# io.net
KiCad netlist of a schematic drawn in EAGLE
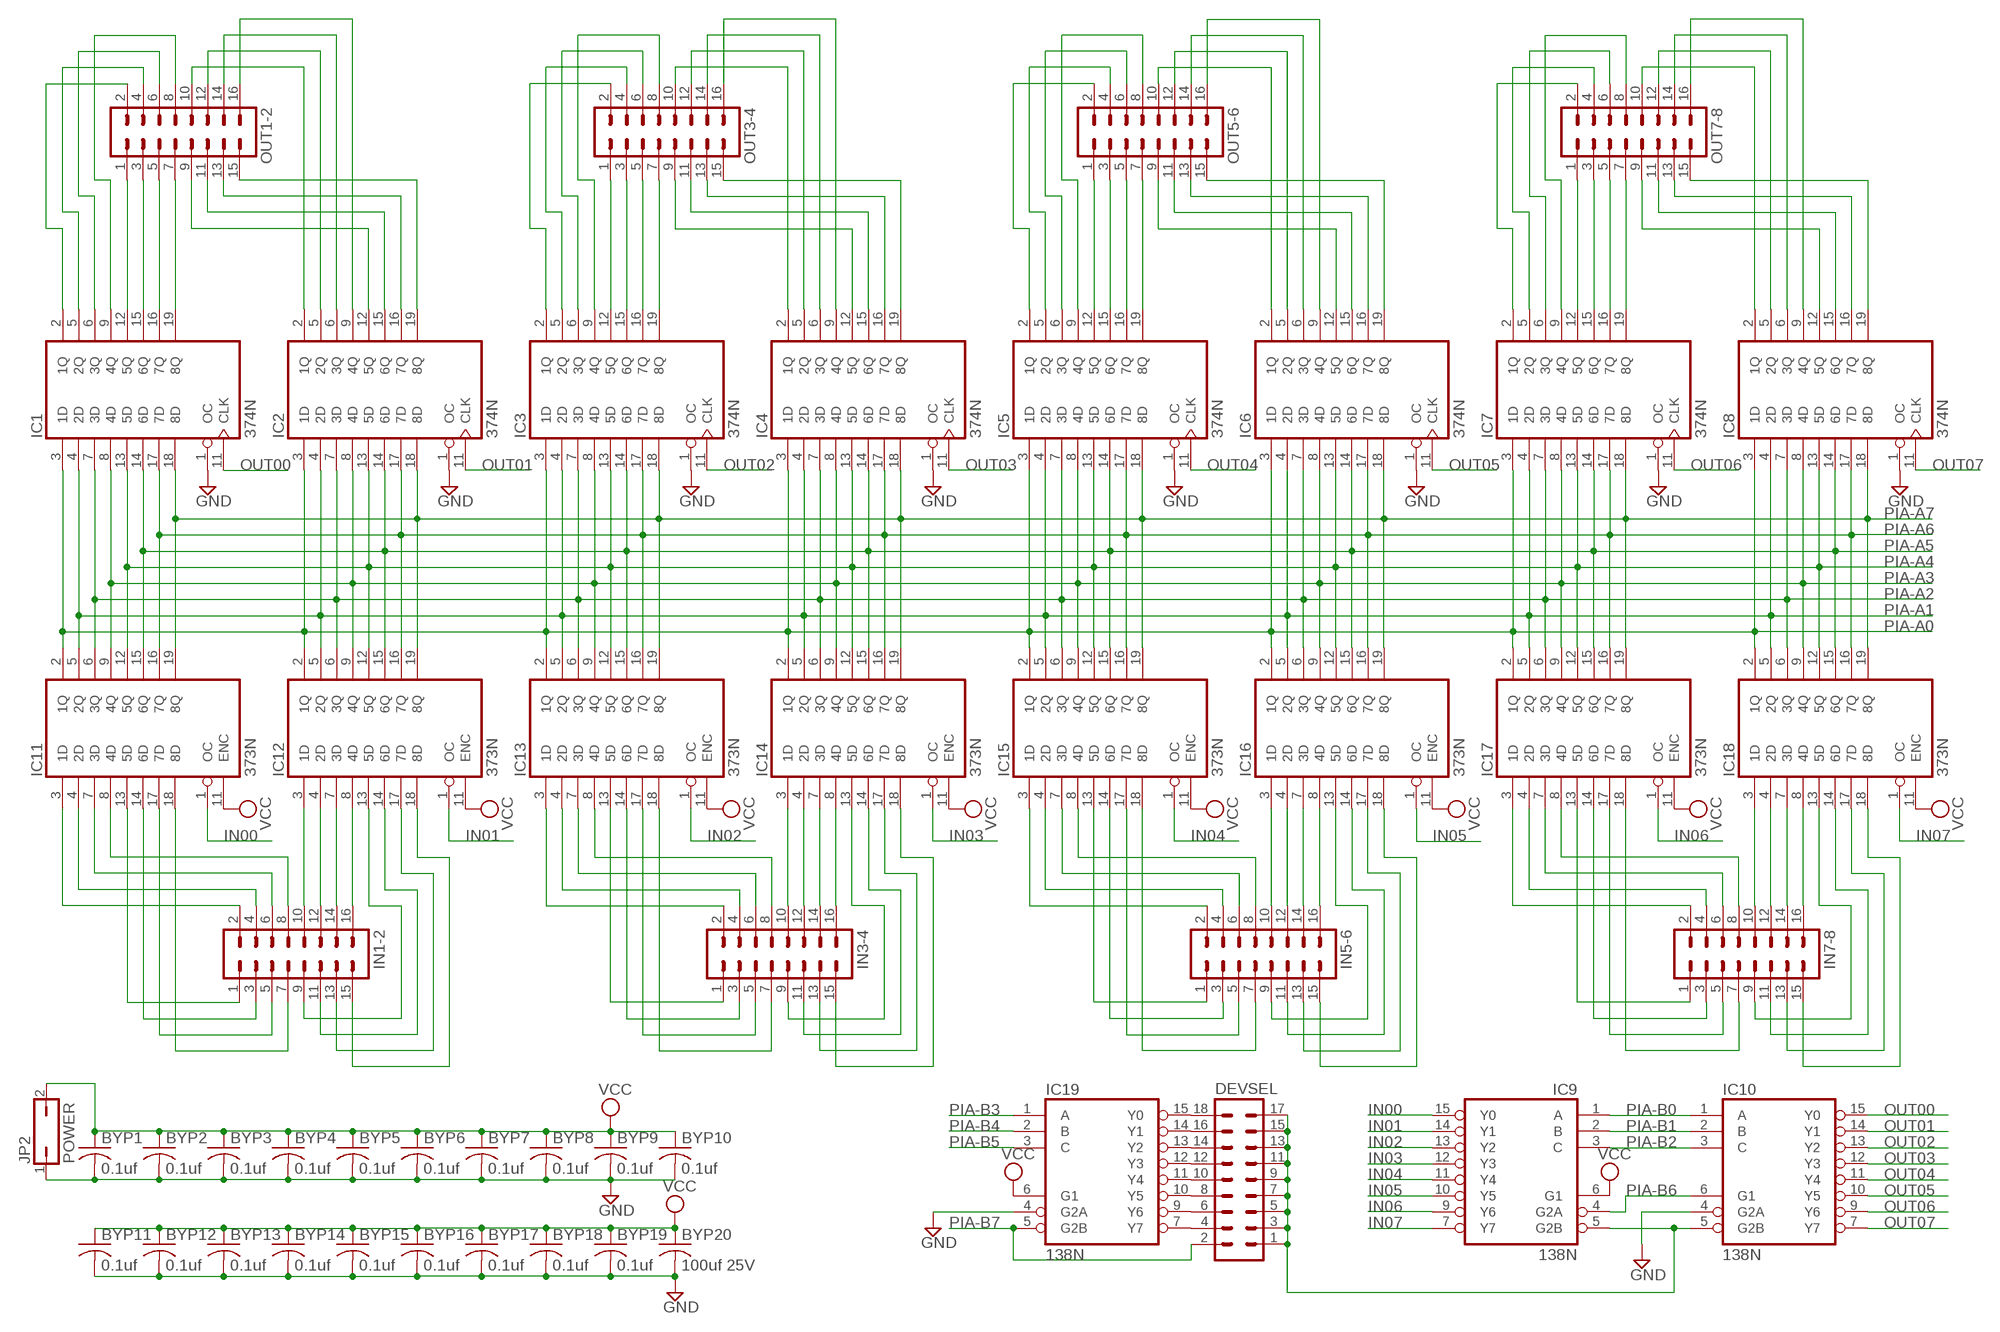
[diagram p0: schematic, sheet 1]
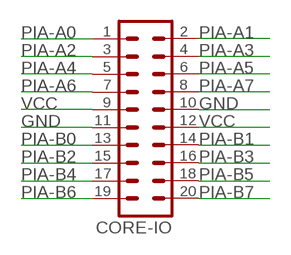
[diagram p1: schematic, sheet 2]

(export (version "E")
  (design (tool "Eeschema 10.0.6"))
  (components
    (comp (ref "CORE-IO")
      (value "MA10-2")
      (footprint "eagle-import:MA10-2")
      (libsource (lib "eagle-import") (part "MA10-2"))
    )
    (comp (ref "BYP1")
      (value "0.1uf")
      (footprint "eagle-import:C050-025X075")
      (libsource (lib "eagle-import") (part "C-US050-025X075"))
    )
    (comp (ref "BYP2")
      (value "0.1uf")
      (footprint "eagle-import:C050-025X075")
      (libsource (lib "eagle-import") (part "C-US050-025X075"))
    )
    (comp (ref "BYP3")
      (value "0.1uf")
      (footprint "eagle-import:C050-025X075")
      (libsource (lib "eagle-import") (part "C-US050-025X075"))
    )
    (comp (ref "BYP4")
      (value "0.1uf")
      (footprint "eagle-import:C050-025X075")
      (libsource (lib "eagle-import") (part "C-US050-025X075"))
    )
    (comp (ref "BYP5")
      (value "0.1uf")
      (footprint "eagle-import:C050-025X075")
      (libsource (lib "eagle-import") (part "C-US050-025X075"))
    )
    (comp (ref "BYP6")
      (value "0.1uf")
      (footprint "eagle-import:C050-025X075")
      (libsource (lib "eagle-import") (part "C-US050-025X075"))
    )
    (comp (ref "BYP7")
      (value "0.1uf")
      (footprint "eagle-import:C050-025X075")
      (libsource (lib "eagle-import") (part "C-US050-025X075"))
    )
    (comp (ref "BYP8")
      (value "0.1uf")
      (footprint "eagle-import:C050-025X075")
      (libsource (lib "eagle-import") (part "C-US050-025X075"))
    )
    (comp (ref "BYP9")
      (value "0.1uf")
      (footprint "eagle-import:C050-025X075")
      (libsource (lib "eagle-import") (part "C-US050-025X075"))
    )
    (comp (ref "BYP10")
      (value "0.1uf")
      (footprint "eagle-import:C050-025X075")
      (libsource (lib "eagle-import") (part "C-US050-025X075"))
    )
    (comp (ref "BYP11")
      (value "0.1uf")
      (footprint "eagle-import:C050-025X075")
      (libsource (lib "eagle-import") (part "C-US050-025X075"))
    )
    (comp (ref "BYP12")
      (value "0.1uf")
      (footprint "eagle-import:C050-025X075")
      (libsource (lib "eagle-import") (part "C-US050-025X075"))
    )
    (comp (ref "BYP13")
      (value "0.1uf")
      (footprint "eagle-import:C050-025X075")
      (libsource (lib "eagle-import") (part "C-US050-025X075"))
    )
    (comp (ref "BYP14")
      (value "0.1uf")
      (footprint "eagle-import:C050-025X075")
      (libsource (lib "eagle-import") (part "C-US050-025X075"))
    )
    (comp (ref "BYP15")
      (value "0.1uf")
      (footprint "eagle-import:C050-025X075")
      (libsource (lib "eagle-import") (part "C-US050-025X075"))
    )
    (comp (ref "BYP16")
      (value "0.1uf")
      (footprint "eagle-import:C050-025X075")
      (libsource (lib "eagle-import") (part "C-US050-025X075"))
    )
    (comp (ref "BYP17")
      (value "0.1uf")
      (footprint "eagle-import:C050-025X075")
      (libsource (lib "eagle-import") (part "C-US050-025X075"))
    )
    (comp (ref "BYP18")
      (value "0.1uf")
      (footprint "eagle-import:C050-025X075")
      (libsource (lib "eagle-import") (part "C-US050-025X075"))
    )
    (comp (ref "BYP19")
      (value "0.1uf")
      (footprint "eagle-import:C050-025X075")
      (libsource (lib "eagle-import") (part "C-US050-025X075"))
    )
    (comp (ref "BYP20")
      (value "100uf 25V")
      (footprint "eagle-import:C150-064X183")
      (libsource (lib "eagle-import") (part "C-US150-064X183"))
    )
    (comp (ref "DEVSEL")
      (value "MA09-2")
      (footprint "eagle-import:MA09-2")
      (libsource (lib "eagle-import") (part "MA09-2"))
    )
    (comp (ref "IC1")
      (value "374N")
      (footprint "eagle-import:DIL20")
      (libsource (lib "eagle-import") (part "74374NLS"))
    )
    (comp (ref "IC2")
      (value "374N")
      (footprint "eagle-import:DIL20")
      (libsource (lib "eagle-import") (part "74374NLS"))
    )
    (comp (ref "IC3")
      (value "374N")
      (footprint "eagle-import:DIL20")
      (libsource (lib "eagle-import") (part "74374NLS"))
    )
    (comp (ref "IC4")
      (value "374N")
      (footprint "eagle-import:DIL20")
      (libsource (lib "eagle-import") (part "74374NLS"))
    )
    (comp (ref "IC5")
      (value "374N")
      (footprint "eagle-import:DIL20")
      (libsource (lib "eagle-import") (part "74374NLS"))
    )
    (comp (ref "IC6")
      (value "374N")
      (footprint "eagle-import:DIL20")
      (libsource (lib "eagle-import") (part "74374NLS"))
    )
    (comp (ref "IC7")
      (value "374N")
      (footprint "eagle-import:DIL20")
      (libsource (lib "eagle-import") (part "74374NLS"))
    )
    (comp (ref "IC8")
      (value "374N")
      (footprint "eagle-import:DIL20")
      (libsource (lib "eagle-import") (part "74374NLS"))
    )
    (comp (ref "IC9")
      (value "138N")
      (footprint "eagle-import:DIL16")
      (libsource (lib "eagle-import") (part "74138NLS"))
    )
    (comp (ref "IC10")
      (value "138N")
      (footprint "eagle-import:DIL16")
      (libsource (lib "eagle-import") (part "74138NLS"))
    )
    (comp (ref "IC11")
      (value "373N")
      (footprint "eagle-import:DIL20")
      (libsource (lib "eagle-import") (part "74373NLS"))
    )
    (comp (ref "IC12")
      (value "373N")
      (footprint "eagle-import:DIL20")
      (libsource (lib "eagle-import") (part "74373NLS"))
    )
    (comp (ref "IC13")
      (value "373N")
      (footprint "eagle-import:DIL20")
      (libsource (lib "eagle-import") (part "74373NLS"))
    )
    (comp (ref "IC14")
      (value "373N")
      (footprint "eagle-import:DIL20")
      (libsource (lib "eagle-import") (part "74373NLS"))
    )
    (comp (ref "IC15")
      (value "373N")
      (footprint "eagle-import:DIL20")
      (libsource (lib "eagle-import") (part "74373NLS"))
    )
    (comp (ref "IC16")
      (value "373N")
      (footprint "eagle-import:DIL20")
      (libsource (lib "eagle-import") (part "74373NLS"))
    )
    (comp (ref "IC17")
      (value "373N")
      (footprint "eagle-import:DIL20")
      (libsource (lib "eagle-import") (part "74373NLS"))
    )
    (comp (ref "IC18")
      (value "373N")
      (footprint "eagle-import:DIL20")
      (libsource (lib "eagle-import") (part "74373NLS"))
    )
    (comp (ref "IC19")
      (value "138N")
      (footprint "eagle-import:DIL16")
      (libsource (lib "eagle-import") (part "74138NLS"))
    )
    (comp (ref "IN1-2")
      (value "MA08-2")
      (footprint "eagle-import:MA08-2")
      (libsource (lib "eagle-import") (part "MA08-2"))
    )
    (comp (ref "IN3-4")
      (value "MA08-2")
      (footprint "eagle-import:MA08-2")
      (libsource (lib "eagle-import") (part "MA08-2"))
    )
    (comp (ref "IN5-6")
      (value "MA08-2")
      (footprint "eagle-import:MA08-2")
      (libsource (lib "eagle-import") (part "MA08-2"))
    )
    (comp (ref "IN7-8")
      (value "MA08-2")
      (footprint "eagle-import:MA08-2")
      (libsource (lib "eagle-import") (part "MA08-2"))
    )
    (comp (ref "JP2")
      (value "POWER")
      (footprint "eagle-import:JP1")
      (libsource (lib "eagle-import") (part "JP1Q"))
    )
    (comp (ref "OUT1-2")
      (value "MA08-2")
      (footprint "eagle-import:MA08-2")
      (libsource (lib "eagle-import") (part "MA08-2"))
    )
    (comp (ref "OUT3-4")
      (value "MA08-2")
      (footprint "eagle-import:MA08-2")
      (libsource (lib "eagle-import") (part "MA08-2"))
    )
    (comp (ref "OUT5-6")
      (value "MA08-2")
      (footprint "eagle-import:MA08-2")
      (libsource (lib "eagle-import") (part "MA08-2"))
    )
    (comp (ref "OUT7-8")
      (value "MA08-2")
      (footprint "eagle-import:MA08-2")
      (libsource (lib "eagle-import") (part "MA08-2"))
    )
  )
  (nets
    (net (code "1") (name "GND") (class "Default")
      (node (ref "BYP1") (pin "2") (pinfunction "2_2") (pintype "passive"))
      (node (ref "BYP10") (pin "2") (pinfunction "2_2") (pintype "passive"))
      (node (ref "BYP11") (pin "2") (pinfunction "2_2") (pintype "passive"))
      (node (ref "BYP12") (pin "2") (pinfunction "2_2") (pintype "passive"))
      (node (ref "BYP13") (pin "2") (pinfunction "2_2") (pintype "passive"))
      (node (ref "BYP14") (pin "2") (pinfunction "2_2") (pintype "passive"))
      (node (ref "BYP15") (pin "2") (pinfunction "2_2") (pintype "passive"))
      (node (ref "BYP16") (pin "2") (pinfunction "2_2") (pintype "passive"))
      (node (ref "BYP17") (pin "2") (pinfunction "2_2") (pintype "passive"))
      (node (ref "BYP18") (pin "2") (pinfunction "2_2") (pintype "passive"))
      (node (ref "BYP19") (pin "2") (pinfunction "2_2") (pintype "passive"))
      (node (ref "BYP2") (pin "2") (pinfunction "2_2") (pintype "passive"))
      (node (ref "BYP20") (pin "2") (pinfunction "2_2") (pintype "passive"))
      (node (ref "BYP3") (pin "2") (pinfunction "2_2") (pintype "passive"))
      (node (ref "BYP4") (pin "2") (pinfunction "2_2") (pintype "passive"))
      (node (ref "BYP5") (pin "2") (pinfunction "2_2") (pintype "passive"))
      (node (ref "BYP6") (pin "2") (pinfunction "2_2") (pintype "passive"))
      (node (ref "BYP7") (pin "2") (pinfunction "2_2") (pintype "passive"))
      (node (ref "BYP8") (pin "2") (pinfunction "2_2") (pintype "passive"))
      (node (ref "BYP9") (pin "2") (pinfunction "2_2") (pintype "passive"))
      (node (ref "CORE-IO") (pin "10") (pinfunction "10_10") (pintype "passive"))
      (node (ref "CORE-IO") (pin "11") (pinfunction "11_11") (pintype "passive"))
      (node (ref "IC1") (pin "1") (pinfunction "OC_1") (pintype "input"))
      (node (ref "IC10") (pin "4") (pinfunction "G2A_4") (pintype "input"))
      (node (ref "IC19") (pin "4") (pinfunction "G2A_4") (pintype "input"))
      (node (ref "IC2") (pin "1") (pinfunction "OC_1") (pintype "input"))
      (node (ref "IC3") (pin "1") (pinfunction "OC_1") (pintype "input"))
      (node (ref "IC4") (pin "1") (pinfunction "OC_1") (pintype "input"))
      (node (ref "IC5") (pin "1") (pinfunction "OC_1") (pintype "input"))
      (node (ref "IC6") (pin "1") (pinfunction "OC_1") (pintype "input"))
      (node (ref "IC7") (pin "1") (pinfunction "OC_1") (pintype "input"))
      (node (ref "IC8") (pin "1") (pinfunction "OC_1") (pintype "input"))
      (node (ref "JP2") (pin "1") (pinfunction "1_1") (pintype "passive"))
    )
    (net (code "2") (name "IN00") (class "Default")
      (node (ref "IC11") (pin "1") (pinfunction "OC_1") (pintype "input"))
      (node (ref "IC9") (pin "15") (pinfunction "Y0_15") (pintype "output"))
    )
    (net (code "3") (name "IN01") (class "Default")
      (node (ref "IC12") (pin "1") (pinfunction "OC_1") (pintype "input"))
      (node (ref "IC9") (pin "14") (pinfunction "Y1_14") (pintype "output"))
    )
    (net (code "4") (name "IN02") (class "Default")
      (node (ref "IC13") (pin "1") (pinfunction "OC_1") (pintype "input"))
      (node (ref "IC9") (pin "13") (pinfunction "Y2_13") (pintype "output"))
    )
    (net (code "5") (name "IN03") (class "Default")
      (node (ref "IC14") (pin "1") (pinfunction "OC_1") (pintype "input"))
      (node (ref "IC9") (pin "12") (pinfunction "Y3_12") (pintype "output"))
    )
    (net (code "6") (name "IN04") (class "Default")
      (node (ref "IC15") (pin "1") (pinfunction "OC_1") (pintype "input"))
      (node (ref "IC9") (pin "11") (pinfunction "Y4_11") (pintype "output"))
    )
    (net (code "7") (name "IN05") (class "Default")
      (node (ref "IC16") (pin "1") (pinfunction "OC_1") (pintype "input"))
      (node (ref "IC9") (pin "10") (pinfunction "Y5_10") (pintype "output"))
    )
    (net (code "8") (name "IN06") (class "Default")
      (node (ref "IC17") (pin "1") (pinfunction "OC_1") (pintype "input"))
      (node (ref "IC9") (pin "9") (pinfunction "Y6_9") (pintype "output"))
    )
    (net (code "9") (name "IN07") (class "Default")
      (node (ref "IC18") (pin "1") (pinfunction "OC_1") (pintype "input"))
      (node (ref "IC9") (pin "7") (pinfunction "Y7_7") (pintype "output"))
    )
    (net (code "10") (name "Net-(IC1A-1Q)") (class "Default")
      (node (ref "IC1") (pin "2") (pinfunction "1Q_2") (pintype "tri_state"))
      (node (ref "OUT1-2") (pin "2") (pinfunction "2_2") (pintype "passive"))
    )
    (net (code "11") (name "Net-(IC1A-2Q)") (class "Default")
      (node (ref "IC1") (pin "5") (pinfunction "2Q_5") (pintype "tri_state"))
      (node (ref "OUT1-2") (pin "4") (pinfunction "4_4") (pintype "passive"))
    )
    (net (code "12") (name "Net-(IC1A-3Q)") (class "Default")
      (node (ref "IC1") (pin "6") (pinfunction "3Q_6") (pintype "tri_state"))
      (node (ref "OUT1-2") (pin "6") (pinfunction "6_6") (pintype "passive"))
    )
    (net (code "13") (name "Net-(IC1A-4Q)") (class "Default")
      (node (ref "IC1") (pin "9") (pinfunction "4Q_9") (pintype "tri_state"))
      (node (ref "OUT1-2") (pin "8") (pinfunction "8_8") (pintype "passive"))
    )
    (net (code "14") (name "Net-(IC1A-5Q)") (class "Default")
      (node (ref "IC1") (pin "12") (pinfunction "5Q_12") (pintype "tri_state"))
      (node (ref "OUT1-2") (pin "1") (pinfunction "1_1") (pintype "passive"))
    )
    (net (code "15") (name "Net-(IC1A-6Q)") (class "Default")
      (node (ref "IC1") (pin "15") (pinfunction "6Q_15") (pintype "tri_state"))
      (node (ref "OUT1-2") (pin "3") (pinfunction "3_3") (pintype "passive"))
    )
    (net (code "16") (name "Net-(IC1A-7Q)") (class "Default")
      (node (ref "IC1") (pin "16") (pinfunction "7Q_16") (pintype "tri_state"))
      (node (ref "OUT1-2") (pin "5") (pinfunction "5_5") (pintype "passive"))
    )
    (net (code "17") (name "Net-(IC1A-8Q)") (class "Default")
      (node (ref "IC1") (pin "19") (pinfunction "8Q_19") (pintype "tri_state"))
      (node (ref "OUT1-2") (pin "7") (pinfunction "7_7") (pintype "passive"))
    )
    (net (code "18") (name "Net-(IC2A-1Q)") (class "Default")
      (node (ref "IC2") (pin "2") (pinfunction "1Q_2") (pintype "tri_state"))
      (node (ref "OUT1-2") (pin "10") (pinfunction "10_10") (pintype "passive"))
    )
    (net (code "19") (name "Net-(IC2A-2Q)") (class "Default")
      (node (ref "IC2") (pin "5") (pinfunction "2Q_5") (pintype "tri_state"))
      (node (ref "OUT1-2") (pin "12") (pinfunction "12_12") (pintype "passive"))
    )
    (net (code "20") (name "Net-(IC2A-3Q)") (class "Default")
      (node (ref "IC2") (pin "6") (pinfunction "3Q_6") (pintype "tri_state"))
      (node (ref "OUT1-2") (pin "14") (pinfunction "14_14") (pintype "passive"))
    )
    (net (code "21") (name "Net-(IC2A-4Q)") (class "Default")
      (node (ref "IC2") (pin "9") (pinfunction "4Q_9") (pintype "tri_state"))
      (node (ref "OUT1-2") (pin "16") (pinfunction "16_16") (pintype "passive"))
    )
    (net (code "22") (name "Net-(IC2A-5Q)") (class "Default")
      (node (ref "IC2") (pin "12") (pinfunction "5Q_12") (pintype "tri_state"))
      (node (ref "OUT1-2") (pin "9") (pinfunction "9_9") (pintype "passive"))
    )
    (net (code "23") (name "Net-(IC2A-6Q)") (class "Default")
      (node (ref "IC2") (pin "15") (pinfunction "6Q_15") (pintype "tri_state"))
      (node (ref "OUT1-2") (pin "11") (pinfunction "11_11") (pintype "passive"))
    )
    (net (code "24") (name "Net-(IC2A-7Q)") (class "Default")
      (node (ref "IC2") (pin "16") (pinfunction "7Q_16") (pintype "tri_state"))
      (node (ref "OUT1-2") (pin "13") (pinfunction "13_13") (pintype "passive"))
    )
    (net (code "25") (name "Net-(IC2A-8Q)") (class "Default")
      (node (ref "IC2") (pin "19") (pinfunction "8Q_19") (pintype "tri_state"))
      (node (ref "OUT1-2") (pin "15") (pinfunction "15_15") (pintype "passive"))
    )
    (net (code "26") (name "Net-(IC3A-1Q)") (class "Default")
      (node (ref "IC3") (pin "2") (pinfunction "1Q_2") (pintype "tri_state"))
      (node (ref "OUT3-4") (pin "2") (pinfunction "2_2") (pintype "passive"))
    )
    (net (code "27") (name "Net-(IC3A-2Q)") (class "Default")
      (node (ref "IC3") (pin "5") (pinfunction "2Q_5") (pintype "tri_state"))
      (node (ref "OUT3-4") (pin "4") (pinfunction "4_4") (pintype "passive"))
    )
    (net (code "28") (name "Net-(IC3A-3Q)") (class "Default")
      (node (ref "IC3") (pin "6") (pinfunction "3Q_6") (pintype "tri_state"))
      (node (ref "OUT3-4") (pin "6") (pinfunction "6_6") (pintype "passive"))
    )
    (net (code "29") (name "Net-(IC3A-4Q)") (class "Default")
      (node (ref "IC3") (pin "9") (pinfunction "4Q_9") (pintype "tri_state"))
      (node (ref "OUT3-4") (pin "8") (pinfunction "8_8") (pintype "passive"))
    )
    (net (code "30") (name "Net-(IC3A-5Q)") (class "Default")
      (node (ref "IC3") (pin "12") (pinfunction "5Q_12") (pintype "tri_state"))
      (node (ref "OUT3-4") (pin "1") (pinfunction "1_1") (pintype "passive"))
    )
    (net (code "31") (name "Net-(IC3A-6Q)") (class "Default")
      (node (ref "IC3") (pin "15") (pinfunction "6Q_15") (pintype "tri_state"))
      (node (ref "OUT3-4") (pin "3") (pinfunction "3_3") (pintype "passive"))
    )
    (net (code "32") (name "Net-(IC3A-7Q)") (class "Default")
      (node (ref "IC3") (pin "16") (pinfunction "7Q_16") (pintype "tri_state"))
      (node (ref "OUT3-4") (pin "5") (pinfunction "5_5") (pintype "passive"))
    )
    (net (code "33") (name "Net-(IC3A-8Q)") (class "Default")
      (node (ref "IC3") (pin "19") (pinfunction "8Q_19") (pintype "tri_state"))
      (node (ref "OUT3-4") (pin "7") (pinfunction "7_7") (pintype "passive"))
    )
    (net (code "34") (name "Net-(IC4A-1Q)") (class "Default")
      (node (ref "IC4") (pin "2") (pinfunction "1Q_2") (pintype "tri_state"))
      (node (ref "OUT3-4") (pin "10") (pinfunction "10_10") (pintype "passive"))
    )
    (net (code "35") (name "Net-(IC4A-2Q)") (class "Default")
      (node (ref "IC4") (pin "5") (pinfunction "2Q_5") (pintype "tri_state"))
      (node (ref "OUT3-4") (pin "12") (pinfunction "12_12") (pintype "passive"))
    )
    (net (code "36") (name "Net-(IC4A-3Q)") (class "Default")
      (node (ref "IC4") (pin "6") (pinfunction "3Q_6") (pintype "tri_state"))
      (node (ref "OUT3-4") (pin "14") (pinfunction "14_14") (pintype "passive"))
    )
    (net (code "37") (name "Net-(IC4A-4Q)") (class "Default")
      (node (ref "IC4") (pin "9") (pinfunction "4Q_9") (pintype "tri_state"))
      (node (ref "OUT3-4") (pin "16") (pinfunction "16_16") (pintype "passive"))
    )
    (net (code "38") (name "Net-(IC4A-5Q)") (class "Default")
      (node (ref "IC4") (pin "12") (pinfunction "5Q_12") (pintype "tri_state"))
      (node (ref "OUT3-4") (pin "9") (pinfunction "9_9") (pintype "passive"))
    )
    (net (code "39") (name "Net-(IC4A-6Q)") (class "Default")
      (node (ref "IC4") (pin "15") (pinfunction "6Q_15") (pintype "tri_state"))
      (node (ref "OUT3-4") (pin "11") (pinfunction "11_11") (pintype "passive"))
    )
    (net (code "40") (name "Net-(IC4A-7Q)") (class "Default")
      (node (ref "IC4") (pin "16") (pinfunction "7Q_16") (pintype "tri_state"))
      (node (ref "OUT3-4") (pin "13") (pinfunction "13_13") (pintype "passive"))
    )
    (net (code "41") (name "Net-(IC4A-8Q)") (class "Default")
      (node (ref "IC4") (pin "19") (pinfunction "8Q_19") (pintype "tri_state"))
      (node (ref "OUT3-4") (pin "15") (pinfunction "15_15") (pintype "passive"))
    )
    (net (code "42") (name "Net-(IC5A-1Q)") (class "Default")
      (node (ref "IC5") (pin "2") (pinfunction "1Q_2") (pintype "tri_state"))
      (node (ref "OUT5-6") (pin "2") (pinfunction "2_2") (pintype "passive"))
    )
    (net (code "43") (name "Net-(IC5A-2Q)") (class "Default")
      (node (ref "IC5") (pin "5") (pinfunction "2Q_5") (pintype "tri_state"))
      (node (ref "OUT5-6") (pin "4") (pinfunction "4_4") (pintype "passive"))
    )
    (net (code "44") (name "Net-(IC5A-3Q)") (class "Default")
      (node (ref "IC5") (pin "6") (pinfunction "3Q_6") (pintype "tri_state"))
      (node (ref "OUT5-6") (pin "6") (pinfunction "6_6") (pintype "passive"))
    )
    (net (code "45") (name "Net-(IC5A-4Q)") (class "Default")
      (node (ref "IC5") (pin "9") (pinfunction "4Q_9") (pintype "tri_state"))
      (node (ref "OUT5-6") (pin "8") (pinfunction "8_8") (pintype "passive"))
    )
    (net (code "46") (name "Net-(IC5A-5Q)") (class "Default")
      (node (ref "IC5") (pin "12") (pinfunction "5Q_12") (pintype "tri_state"))
      (node (ref "OUT5-6") (pin "1") (pinfunction "1_1") (pintype "passive"))
    )
    (net (code "47") (name "Net-(IC5A-6Q)") (class "Default")
      (node (ref "IC5") (pin "15") (pinfunction "6Q_15") (pintype "tri_state"))
      (node (ref "OUT5-6") (pin "3") (pinfunction "3_3") (pintype "passive"))
    )
    (net (code "48") (name "Net-(IC5A-7Q)") (class "Default")
      (node (ref "IC5") (pin "16") (pinfunction "7Q_16") (pintype "tri_state"))
      (node (ref "OUT5-6") (pin "5") (pinfunction "5_5") (pintype "passive"))
    )
    (net (code "49") (name "Net-(IC5A-8Q)") (class "Default")
      (node (ref "IC5") (pin "19") (pinfunction "8Q_19") (pintype "tri_state"))
      (node (ref "OUT5-6") (pin "7") (pinfunction "7_7") (pintype "passive"))
    )
    (net (code "50") (name "Net-(IC6A-1Q)") (class "Default")
      (node (ref "IC6") (pin "2") (pinfunction "1Q_2") (pintype "tri_state"))
      (node (ref "OUT5-6") (pin "10") (pinfunction "10_10") (pintype "passive"))
    )
    (net (code "51") (name "Net-(IC6A-2Q)") (class "Default")
      (node (ref "IC6") (pin "5") (pinfunction "2Q_5") (pintype "tri_state"))
      (node (ref "OUT5-6") (pin "12") (pinfunction "12_12") (pintype "passive"))
    )
    (net (code "52") (name "Net-(IC6A-3Q)") (class "Default")
      (node (ref "IC6") (pin "6") (pinfunction "3Q_6") (pintype "tri_state"))
      (node (ref "OUT5-6") (pin "14") (pinfunction "14_14") (pintype "passive"))
    )
    (net (code "53") (name "Net-(IC6A-4Q)") (class "Default")
      (node (ref "IC6") (pin "9") (pinfunction "4Q_9") (pintype "tri_state"))
      (node (ref "OUT5-6") (pin "16") (pinfunction "16_16") (pintype "passive"))
    )
    (net (code "54") (name "Net-(IC6A-5Q)") (class "Default")
      (node (ref "IC6") (pin "12") (pinfunction "5Q_12") (pintype "tri_state"))
      (node (ref "OUT5-6") (pin "9") (pinfunction "9_9") (pintype "passive"))
    )
    (net (code "55") (name "Net-(IC6A-6Q)") (class "Default")
      (node (ref "IC6") (pin "15") (pinfunction "6Q_15") (pintype "tri_state"))
      (node (ref "OUT5-6") (pin "11") (pinfunction "11_11") (pintype "passive"))
    )
    (net (code "56") (name "Net-(IC6A-7Q)") (class "Default")
      (node (ref "IC6") (pin "16") (pinfunction "7Q_16") (pintype "tri_state"))
      (node (ref "OUT5-6") (pin "13") (pinfunction "13_13") (pintype "passive"))
    )
    (net (code "57") (name "Net-(IC6A-8Q)") (class "Default")
      (node (ref "IC6") (pin "19") (pinfunction "8Q_19") (pintype "tri_state"))
      (node (ref "OUT5-6") (pin "15") (pinfunction "15_15") (pintype "passive"))
    )
    (net (code "58") (name "Net-(IC7A-1Q)") (class "Default")
      (node (ref "IC7") (pin "2") (pinfunction "1Q_2") (pintype "tri_state"))
      (node (ref "OUT7-8") (pin "2") (pinfunction "2_2") (pintype "passive"))
    )
    (net (code "59") (name "Net-(IC7A-2Q)") (class "Default")
      (node (ref "IC7") (pin "5") (pinfunction "2Q_5") (pintype "tri_state"))
      (node (ref "OUT7-8") (pin "4") (pinfunction "4_4") (pintype "passive"))
    )
    (net (code "60") (name "Net-(IC7A-3Q)") (class "Default")
      (node (ref "IC7") (pin "6") (pinfunction "3Q_6") (pintype "tri_state"))
      (node (ref "OUT7-8") (pin "6") (pinfunction "6_6") (pintype "passive"))
    )
    (net (code "61") (name "Net-(IC7A-4Q)") (class "Default")
      (node (ref "IC7") (pin "9") (pinfunction "4Q_9") (pintype "tri_state"))
      (node (ref "OUT7-8") (pin "8") (pinfunction "8_8") (pintype "passive"))
    )
    (net (code "62") (name "Net-(IC7A-5Q)") (class "Default")
      (node (ref "IC7") (pin "12") (pinfunction "5Q_12") (pintype "tri_state"))
      (node (ref "OUT7-8") (pin "1") (pinfunction "1_1") (pintype "passive"))
    )
    (net (code "63") (name "Net-(IC7A-6Q)") (class "Default")
      (node (ref "IC7") (pin "15") (pinfunction "6Q_15") (pintype "tri_state"))
      (node (ref "OUT7-8") (pin "3") (pinfunction "3_3") (pintype "passive"))
    )
    (net (code "64") (name "Net-(IC7A-7Q)") (class "Default")
      (node (ref "IC7") (pin "16") (pinfunction "7Q_16") (pintype "tri_state"))
      (node (ref "OUT7-8") (pin "5") (pinfunction "5_5") (pintype "passive"))
    )
    (net (code "65") (name "Net-(IC7A-8Q)") (class "Default")
      (node (ref "IC7") (pin "19") (pinfunction "8Q_19") (pintype "tri_state"))
      (node (ref "OUT7-8") (pin "7") (pinfunction "7_7") (pintype "passive"))
    )
    (net (code "66") (name "Net-(IC8A-1Q)") (class "Default")
      (node (ref "IC8") (pin "2") (pinfunction "1Q_2") (pintype "tri_state"))
      (node (ref "OUT7-8") (pin "10") (pinfunction "10_10") (pintype "passive"))
    )
    (net (code "67") (name "Net-(IC8A-2Q)") (class "Default")
      (node (ref "IC8") (pin "5") (pinfunction "2Q_5") (pintype "tri_state"))
      (node (ref "OUT7-8") (pin "12") (pinfunction "12_12") (pintype "passive"))
    )
    (net (code "68") (name "Net-(IC8A-3Q)") (class "Default")
      (node (ref "IC8") (pin "6") (pinfunction "3Q_6") (pintype "tri_state"))
      (node (ref "OUT7-8") (pin "14") (pinfunction "14_14") (pintype "passive"))
    )
    (net (code "69") (name "Net-(IC8A-4Q)") (class "Default")
      (node (ref "IC8") (pin "9") (pinfunction "4Q_9") (pintype "tri_state"))
      (node (ref "OUT7-8") (pin "16") (pinfunction "16_16") (pintype "passive"))
    )
    (net (code "70") (name "Net-(IC8A-5Q)") (class "Default")
      (node (ref "IC8") (pin "12") (pinfunction "5Q_12") (pintype "tri_state"))
      (node (ref "OUT7-8") (pin "9") (pinfunction "9_9") (pintype "passive"))
    )
    (net (code "71") (name "Net-(IC8A-6Q)") (class "Default")
      (node (ref "IC8") (pin "15") (pinfunction "6Q_15") (pintype "tri_state"))
      (node (ref "OUT7-8") (pin "11") (pinfunction "11_11") (pintype "passive"))
    )
    (net (code "72") (name "Net-(IC8A-7Q)") (class "Default")
      (node (ref "IC8") (pin "16") (pinfunction "7Q_16") (pintype "tri_state"))
      (node (ref "OUT7-8") (pin "13") (pinfunction "13_13") (pintype "passive"))
    )
    (net (code "73") (name "Net-(IC8A-8Q)") (class "Default")
      (node (ref "IC8") (pin "19") (pinfunction "8Q_19") (pintype "tri_state"))
      (node (ref "OUT7-8") (pin "15") (pinfunction "15_15") (pintype "passive"))
    )
    (net (code "74") (name "Net-(IC10A-G2B)") (class "Default")
      (node (ref "DEVSEL") (pin "1") (pinfunction "1_1") (pintype "passive"))
      (node (ref "DEVSEL") (pin "11") (pinfunction "11_11") (pintype "passive"))
      (node (ref "DEVSEL") (pin "13") (pinfunction "13_13") (pintype "passive"))
      (node (ref "DEVSEL") (pin "15") (pinfunction "15_15") (pintype "passive"))
      (node (ref "DEVSEL") (pin "17") (pinfunction "17_17") (pintype "passive"))
      (node (ref "DEVSEL") (pin "3") (pinfunction "3_3") (pintype "passive"))
      (node (ref "DEVSEL") (pin "5") (pinfunction "5_5") (pintype "passive"))
      (node (ref "DEVSEL") (pin "7") (pinfunction "7_7") (pintype "passive"))
      (node (ref "DEVSEL") (pin "9") (pinfunction "9_9") (pintype "passive"))
      (node (ref "IC10") (pin "5") (pinfunction "G2B_5") (pintype "input"))
      (node (ref "IC9") (pin "5") (pinfunction "G2B_5") (pintype "input"))
    )
    (net (code "75") (name "Net-(IC11A-1D)") (class "Default")
      (node (ref "IC11") (pin "3") (pinfunction "1D_3") (pintype "input"))
      (node (ref "IN1-2") (pin "2") (pinfunction "2_2") (pintype "passive"))
    )
    (net (code "76") (name "Net-(IC11A-2D)") (class "Default")
      (node (ref "IC11") (pin "4") (pinfunction "2D_4") (pintype "input"))
      (node (ref "IN1-2") (pin "4") (pinfunction "4_4") (pintype "passive"))
    )
    (net (code "77") (name "Net-(IC11A-3D)") (class "Default")
      (node (ref "IC11") (pin "7") (pinfunction "3D_7") (pintype "input"))
      (node (ref "IN1-2") (pin "6") (pinfunction "6_6") (pintype "passive"))
    )
    (net (code "78") (name "Net-(IC11A-4D)") (class "Default")
      (node (ref "IC11") (pin "8") (pinfunction "4D_8") (pintype "input"))
      (node (ref "IN1-2") (pin "8") (pinfunction "8_8") (pintype "passive"))
    )
    (net (code "79") (name "Net-(IC11A-5D)") (class "Default")
      (node (ref "IC11") (pin "13") (pinfunction "5D_13") (pintype "input"))
      (node (ref "IN1-2") (pin "1") (pinfunction "1_1") (pintype "passive"))
    )
    (net (code "80") (name "Net-(IC11A-6D)") (class "Default")
      (node (ref "IC11") (pin "14") (pinfunction "6D_14") (pintype "input"))
      (node (ref "IN1-2") (pin "3") (pinfunction "3_3") (pintype "passive"))
    )
    (net (code "81") (name "Net-(IC11A-7D)") (class "Default")
      (node (ref "IC11") (pin "17") (pinfunction "7D_17") (pintype "input"))
      (node (ref "IN1-2") (pin "5") (pinfunction "5_5") (pintype "passive"))
    )
    (net (code "82") (name "Net-(IC11A-8D)") (class "Default")
      (node (ref "IC11") (pin "18") (pinfunction "8D_18") (pintype "input"))
      (node (ref "IN1-2") (pin "7") (pinfunction "7_7") (pintype "passive"))
    )
    (net (code "83") (name "Net-(IC12A-1D)") (class "Default")
      (node (ref "IC12") (pin "3") (pinfunction "1D_3") (pintype "input"))
      (node (ref "IN1-2") (pin "10") (pinfunction "10_10") (pintype "passive"))
    )
    (net (code "84") (name "Net-(IC12A-2D)") (class "Default")
      (node (ref "IC12") (pin "4") (pinfunction "2D_4") (pintype "input"))
      (node (ref "IN1-2") (pin "12") (pinfunction "12_12") (pintype "passive"))
    )
    (net (code "85") (name "Net-(IC12A-3D)") (class "Default")
      (node (ref "IC12") (pin "7") (pinfunction "3D_7") (pintype "input"))
      (node (ref "IN1-2") (pin "14") (pinfunction "14_14") (pintype "passive"))
    )
    (net (code "86") (name "Net-(IC12A-4D)") (class "Default")
      (node (ref "IC12") (pin "8") (pinfunction "4D_8") (pintype "input"))
      (node (ref "IN1-2") (pin "16") (pinfunction "16_16") (pintype "passive"))
    )
    (net (code "87") (name "Net-(IC12A-5D)") (class "Default")
      (node (ref "IC12") (pin "13") (pinfunction "5D_13") (pintype "input"))
      (node (ref "IN1-2") (pin "9") (pinfunction "9_9") (pintype "passive"))
    )
    (net (code "88") (name "Net-(IC12A-6D)") (class "Default")
      (node (ref "IC12") (pin "14") (pinfunction "6D_14") (pintype "input"))
      (node (ref "IN1-2") (pin "11") (pinfunction "11_11") (pintype "passive"))
    )
    (net (code "89") (name "Net-(IC12A-7D)") (class "Default")
      (node (ref "IC12") (pin "17") (pinfunction "7D_17") (pintype "input"))
      (node (ref "IN1-2") (pin "13") (pinfunction "13_13") (pintype "passive"))
    )
    (net (code "90") (name "Net-(IC12A-8D)") (class "Default")
      (node (ref "IC12") (pin "18") (pinfunction "8D_18") (pintype "input"))
      (node (ref "IN1-2") (pin "15") (pinfunction "15_15") (pintype "passive"))
    )
    (net (code "91") (name "Net-(IC13A-1D)") (class "Default")
      (node (ref "IC13") (pin "3") (pinfunction "1D_3") (pintype "input"))
      (node (ref "IN3-4") (pin "2") (pinfunction "2_2") (pintype "passive"))
    )
    (net (code "92") (name "Net-(IC13A-2D)") (class "Default")
      (node (ref "IC13") (pin "4") (pinfunction "2D_4") (pintype "input"))
      (node (ref "IN3-4") (pin "4") (pinfunction "4_4") (pintype "passive"))
    )
    (net (code "93") (name "Net-(IC13A-3D)") (class "Default")
      (node (ref "IC13") (pin "7") (pinfunction "3D_7") (pintype "input"))
      (node (ref "IN3-4") (pin "6") (pinfunction "6_6") (pintype "passive"))
    )
    (net (code "94") (name "Net-(IC13A-4D)") (class "Default")
      (node (ref "IC13") (pin "8") (pinfunction "4D_8") (pintype "input"))
      (node (ref "IN3-4") (pin "8") (pinfunction "8_8") (pintype "passive"))
    )
    (net (code "95") (name "Net-(IC13A-5D)") (class "Default")
      (node (ref "IC13") (pin "13") (pinfunction "5D_13") (pintype "input"))
      (node (ref "IN3-4") (pin "1") (pinfunction "1_1") (pintype "passive"))
    )
    (net (code "96") (name "Net-(IC13A-6D)") (class "Default")
      (node (ref "IC13") (pin "14") (pinfunction "6D_14") (pintype "input"))
      (node (ref "IN3-4") (pin "3") (pinfunction "3_3") (pintype "passive"))
    )
    (net (code "97") (name "Net-(IC13A-7D)") (class "Default")
      (node (ref "IC13") (pin "17") (pinfunction "7D_17") (pintype "input"))
      (node (ref "IN3-4") (pin "5") (pinfunction "5_5") (pintype "passive"))
    )
    (net (code "98") (name "Net-(IC13A-8D)") (class "Default")
      (node (ref "IC13") (pin "18") (pinfunction "8D_18") (pintype "input"))
      (node (ref "IN3-4") (pin "7") (pinfunction "7_7") (pintype "passive"))
    )
    (net (code "99") (name "Net-(IC14A-1D)") (class "Default")
      (node (ref "IC14") (pin "3") (pinfunction "1D_3") (pintype "input"))
      (node (ref "IN3-4") (pin "10") (pinfunction "10_10") (pintype "passive"))
    )
    (net (code "100") (name "Net-(IC14A-2D)") (class "Default")
      (node (ref "IC14") (pin "4") (pinfunction "2D_4") (pintype "input"))
      (node (ref "IN3-4") (pin "12") (pinfunction "12_12") (pintype "passive"))
    )
    (net (code "101") (name "Net-(IC14A-3D)") (class "Default")
      (node (ref "IC14") (pin "7") (pinfunction "3D_7") (pintype "input"))
      (node (ref "IN3-4") (pin "14") (pinfunction "14_14") (pintype "passive"))
    )
    (net (code "102") (name "Net-(IC14A-4D)") (class "Default")
      (node (ref "IC14") (pin "8") (pinfunction "4D_8") (pintype "input"))
      (node (ref "IN3-4") (pin "16") (pinfunction "16_16") (pintype "passive"))
    )
    (net (code "103") (name "Net-(IC14A-5D)") (class "Default")
      (node (ref "IC14") (pin "13") (pinfunction "5D_13") (pintype "input"))
      (node (ref "IN3-4") (pin "9") (pinfunction "9_9") (pintype "passive"))
    )
    (net (code "104") (name "Net-(IC14A-6D)") (class "Default")
      (node (ref "IC14") (pin "14") (pinfunction "6D_14") (pintype "input"))
      (node (ref "IN3-4") (pin "11") (pinfunction "11_11") (pintype "passive"))
    )
    (net (code "105") (name "Net-(IC14A-7D)") (class "Default")
      (node (ref "IC14") (pin "17") (pinfunction "7D_17") (pintype "input"))
      (node (ref "IN3-4") (pin "13") (pinfunction "13_13") (pintype "passive"))
    )
    (net (code "106") (name "Net-(IC14A-8D)") (class "Default")
      (node (ref "IC14") (pin "18") (pinfunction "8D_18") (pintype "input"))
      (node (ref "IN3-4") (pin "15") (pinfunction "15_15") (pintype "passive"))
    )
    (net (code "107") (name "Net-(IC15A-1D)") (class "Default")
      (node (ref "IC15") (pin "3") (pinfunction "1D_3") (pintype "input"))
      (node (ref "IN5-6") (pin "2") (pinfunction "2_2") (pintype "passive"))
    )
    (net (code "108") (name "Net-(IC15A-2D)") (class "Default")
      (node (ref "IC15") (pin "4") (pinfunction "2D_4") (pintype "input"))
      (node (ref "IN5-6") (pin "4") (pinfunction "4_4") (pintype "passive"))
    )
    (net (code "109") (name "Net-(IC15A-3D)") (class "Default")
      (node (ref "IC15") (pin "7") (pinfunction "3D_7") (pintype "input"))
      (node (ref "IN5-6") (pin "6") (pinfunction "6_6") (pintype "passive"))
    )
    (net (code "110") (name "Net-(IC15A-4D)") (class "Default")
      (node (ref "IC15") (pin "8") (pinfunction "4D_8") (pintype "input"))
      (node (ref "IN5-6") (pin "8") (pinfunction "8_8") (pintype "passive"))
    )
    (net (code "111") (name "Net-(IC15A-5D)") (class "Default")
      (node (ref "IC15") (pin "13") (pinfunction "5D_13") (pintype "input"))
      (node (ref "IN5-6") (pin "1") (pinfunction "1_1") (pintype "passive"))
    )
    (net (code "112") (name "Net-(IC15A-6D)") (class "Default")
      (node (ref "IC15") (pin "14") (pinfunction "6D_14") (pintype "input"))
      (node (ref "IN5-6") (pin "3") (pinfunction "3_3") (pintype "passive"))
    )
    (net (code "113") (name "Net-(IC15A-7D)") (class "Default")
      (node (ref "IC15") (pin "17") (pinfunction "7D_17") (pintype "input"))
      (node (ref "IN5-6") (pin "5") (pinfunction "5_5") (pintype "passive"))
    )
    (net (code "114") (name "Net-(IC15A-8D)") (class "Default")
      (node (ref "IC15") (pin "18") (pinfunction "8D_18") (pintype "input"))
      (node (ref "IN5-6") (pin "7") (pinfunction "7_7") (pintype "passive"))
    )
    (net (code "115") (name "Net-(IC16A-1D)") (class "Default")
      (node (ref "IC16") (pin "3") (pinfunction "1D_3") (pintype "input"))
      (node (ref "IN5-6") (pin "10") (pinfunction "10_10") (pintype "passive"))
    )
    (net (code "116") (name "Net-(IC16A-2D)") (class "Default")
      (node (ref "IC16") (pin "4") (pinfunction "2D_4") (pintype "input"))
      (node (ref "IN5-6") (pin "12") (pinfunction "12_12") (pintype "passive"))
    )
    (net (code "117") (name "Net-(IC16A-3D)") (class "Default")
      (node (ref "IC16") (pin "7") (pinfunction "3D_7") (pintype "input"))
      (node (ref "IN5-6") (pin "14") (pinfunction "14_14") (pintype "passive"))
    )
    (net (code "118") (name "Net-(IC16A-4D)") (class "Default")
      (node (ref "IC16") (pin "8") (pinfunction "4D_8") (pintype "input"))
      (node (ref "IN5-6") (pin "16") (pinfunction "16_16") (pintype "passive"))
    )
    (net (code "119") (name "Net-(IC16A-5D)") (class "Default")
      (node (ref "IC16") (pin "13") (pinfunction "5D_13") (pintype "input"))
      (node (ref "IN5-6") (pin "9") (pinfunction "9_9") (pintype "passive"))
    )
    (net (code "120") (name "Net-(IC16A-6D)") (class "Default")
      (node (ref "IC16") (pin "14") (pinfunction "6D_14") (pintype "input"))
      (node (ref "IN5-6") (pin "11") (pinfunction "11_11") (pintype "passive"))
    )
    (net (code "121") (name "Net-(IC16A-7D)") (class "Default")
      (node (ref "IC16") (pin "17") (pinfunction "7D_17") (pintype "input"))
      (node (ref "IN5-6") (pin "13") (pinfunction "13_13") (pintype "passive"))
    )
    (net (code "122") (name "Net-(IC16A-8D)") (class "Default")
      (node (ref "IC16") (pin "18") (pinfunction "8D_18") (pintype "input"))
      (node (ref "IN5-6") (pin "15") (pinfunction "15_15") (pintype "passive"))
    )
    (net (code "123") (name "Net-(IC17A-1D)") (class "Default")
      (node (ref "IC17") (pin "3") (pinfunction "1D_3") (pintype "input"))
      (node (ref "IN7-8") (pin "2") (pinfunction "2_2") (pintype "passive"))
    )
    (net (code "124") (name "Net-(IC17A-2D)") (class "Default")
      (node (ref "IC17") (pin "4") (pinfunction "2D_4") (pintype "input"))
      (node (ref "IN7-8") (pin "4") (pinfunction "4_4") (pintype "passive"))
    )
    (net (code "125") (name "Net-(IC17A-3D)") (class "Default")
      (node (ref "IC17") (pin "7") (pinfunction "3D_7") (pintype "input"))
      (node (ref "IN7-8") (pin "6") (pinfunction "6_6") (pintype "passive"))
    )
    (net (code "126") (name "Net-(IC17A-4D)") (class "Default")
      (node (ref "IC17") (pin "8") (pinfunction "4D_8") (pintype "input"))
      (node (ref "IN7-8") (pin "8") (pinfunction "8_8") (pintype "passive"))
    )
    (net (code "127") (name "Net-(IC17A-5D)") (class "Default")
      (node (ref "IC17") (pin "13") (pinfunction "5D_13") (pintype "input"))
      (node (ref "IN7-8") (pin "1") (pinfunction "1_1") (pintype "passive"))
    )
    (net (code "128") (name "Net-(IC17A-6D)") (class "Default")
      (node (ref "IC17") (pin "14") (pinfunction "6D_14") (pintype "input"))
      (node (ref "IN7-8") (pin "3") (pinfunction "3_3") (pintype "passive"))
    )
    (net (code "129") (name "Net-(IC17A-7D)") (class "Default")
      (node (ref "IC17") (pin "17") (pinfunction "7D_17") (pintype "input"))
      (node (ref "IN7-8") (pin "5") (pinfunction "5_5") (pintype "passive"))
    )
    (net (code "130") (name "Net-(IC17A-8D)") (class "Default")
      (node (ref "IC17") (pin "18") (pinfunction "8D_18") (pintype "input"))
      (node (ref "IN7-8") (pin "7") (pinfunction "7_7") (pintype "passive"))
    )
    (net (code "131") (name "Net-(IC18A-1D)") (class "Default")
      (node (ref "IC18") (pin "3") (pinfunction "1D_3") (pintype "input"))
      (node (ref "IN7-8") (pin "10") (pinfunction "10_10") (pintype "passive"))
    )
    (net (code "132") (name "Net-(IC18A-2D)") (class "Default")
      (node (ref "IC18") (pin "4") (pinfunction "2D_4") (pintype "input"))
      (node (ref "IN7-8") (pin "12") (pinfunction "12_12") (pintype "passive"))
    )
    (net (code "133") (name "Net-(IC18A-3D)") (class "Default")
      (node (ref "IC18") (pin "7") (pinfunction "3D_7") (pintype "input"))
      (node (ref "IN7-8") (pin "14") (pinfunction "14_14") (pintype "passive"))
    )
    (net (code "134") (name "Net-(IC18A-4D)") (class "Default")
      (node (ref "IC18") (pin "8") (pinfunction "4D_8") (pintype "input"))
      (node (ref "IN7-8") (pin "16") (pinfunction "16_16") (pintype "passive"))
    )
    (net (code "135") (name "Net-(IC18A-5D)") (class "Default")
      (node (ref "IC18") (pin "13") (pinfunction "5D_13") (pintype "input"))
      (node (ref "IN7-8") (pin "9") (pinfunction "9_9") (pintype "passive"))
    )
    (net (code "136") (name "Net-(IC18A-6D)") (class "Default")
      (node (ref "IC18") (pin "14") (pinfunction "6D_14") (pintype "input"))
      (node (ref "IN7-8") (pin "11") (pinfunction "11_11") (pintype "passive"))
    )
    (net (code "137") (name "Net-(IC18A-7D)") (class "Default")
      (node (ref "IC18") (pin "17") (pinfunction "7D_17") (pintype "input"))
      (node (ref "IN7-8") (pin "13") (pinfunction "13_13") (pintype "passive"))
    )
    (net (code "138") (name "Net-(IC18A-8D)") (class "Default")
      (node (ref "IC18") (pin "18") (pinfunction "8D_18") (pintype "input"))
      (node (ref "IN7-8") (pin "15") (pinfunction "15_15") (pintype "passive"))
    )
    (net (code "139") (name "Net-(IC19A-Y0)") (class "Default")
      (node (ref "DEVSEL") (pin "18") (pinfunction "18_18") (pintype "passive"))
      (node (ref "IC19") (pin "15") (pinfunction "Y0_15") (pintype "output"))
    )
    (net (code "140") (name "Net-(IC19A-Y1)") (class "Default")
      (node (ref "DEVSEL") (pin "16") (pinfunction "16_16") (pintype "passive"))
      (node (ref "IC19") (pin "14") (pinfunction "Y1_14") (pintype "output"))
    )
    (net (code "141") (name "Net-(IC19A-Y2)") (class "Default")
      (node (ref "DEVSEL") (pin "14") (pinfunction "14_14") (pintype "passive"))
      (node (ref "IC19") (pin "13") (pinfunction "Y2_13") (pintype "output"))
    )
    (net (code "142") (name "Net-(IC19A-Y3)") (class "Default")
      (node (ref "DEVSEL") (pin "12") (pinfunction "12_12") (pintype "passive"))
      (node (ref "IC19") (pin "12") (pinfunction "Y3_12") (pintype "output"))
    )
    (net (code "143") (name "Net-(IC19A-Y4)") (class "Default")
      (node (ref "DEVSEL") (pin "10") (pinfunction "10_10") (pintype "passive"))
      (node (ref "IC19") (pin "11") (pinfunction "Y4_11") (pintype "output"))
    )
    (net (code "144") (name "Net-(IC19A-Y5)") (class "Default")
      (node (ref "DEVSEL") (pin "8") (pinfunction "8_8") (pintype "passive"))
      (node (ref "IC19") (pin "10") (pinfunction "Y5_10") (pintype "output"))
    )
    (net (code "145") (name "Net-(IC19A-Y6)") (class "Default")
      (node (ref "DEVSEL") (pin "6") (pinfunction "6_6") (pintype "passive"))
      (node (ref "IC19") (pin "9") (pinfunction "Y6_9") (pintype "output"))
    )
    (net (code "146") (name "Net-(IC19A-Y7)") (class "Default")
      (node (ref "DEVSEL") (pin "4") (pinfunction "4_4") (pintype "passive"))
      (node (ref "IC19") (pin "7") (pinfunction "Y7_7") (pintype "output"))
    )
    (net (code "147") (name "OUT00") (class "Default")
      (node (ref "IC1") (pin "11") (pinfunction "CLK_11") (pintype "input"))
      (node (ref "IC10") (pin "15") (pinfunction "Y0_15") (pintype "output"))
    )
    (net (code "148") (name "OUT01") (class "Default")
      (node (ref "IC10") (pin "14") (pinfunction "Y1_14") (pintype "output"))
      (node (ref "IC2") (pin "11") (pinfunction "CLK_11") (pintype "input"))
    )
    (net (code "149") (name "OUT02") (class "Default")
      (node (ref "IC10") (pin "13") (pinfunction "Y2_13") (pintype "output"))
      (node (ref "IC3") (pin "11") (pinfunction "CLK_11") (pintype "input"))
    )
    (net (code "150") (name "OUT03") (class "Default")
      (node (ref "IC10") (pin "12") (pinfunction "Y3_12") (pintype "output"))
      (node (ref "IC4") (pin "11") (pinfunction "CLK_11") (pintype "input"))
    )
    (net (code "151") (name "OUT04") (class "Default")
      (node (ref "IC10") (pin "11") (pinfunction "Y4_11") (pintype "output"))
      (node (ref "IC5") (pin "11") (pinfunction "CLK_11") (pintype "input"))
    )
    (net (code "152") (name "OUT05") (class "Default")
      (node (ref "IC10") (pin "10") (pinfunction "Y5_10") (pintype "output"))
      (node (ref "IC6") (pin "11") (pinfunction "CLK_11") (pintype "input"))
    )
    (net (code "153") (name "OUT06") (class "Default")
      (node (ref "IC10") (pin "9") (pinfunction "Y6_9") (pintype "output"))
      (node (ref "IC7") (pin "11") (pinfunction "CLK_11") (pintype "input"))
    )
    (net (code "154") (name "OUT07") (class "Default")
      (node (ref "IC10") (pin "7") (pinfunction "Y7_7") (pintype "output"))
      (node (ref "IC8") (pin "11") (pinfunction "CLK_11") (pintype "input"))
    )
    (net (code "155") (name "PIA-A0") (class "Default")
      (node (ref "CORE-IO") (pin "1") (pinfunction "1_1") (pintype "passive"))
      (node (ref "IC1") (pin "3") (pinfunction "1D_3") (pintype "input"))
      (node (ref "IC11") (pin "2") (pinfunction "1Q_2") (pintype "tri_state"))
      (node (ref "IC12") (pin "2") (pinfunction "1Q_2") (pintype "tri_state"))
      (node (ref "IC13") (pin "2") (pinfunction "1Q_2") (pintype "tri_state"))
      (node (ref "IC14") (pin "2") (pinfunction "1Q_2") (pintype "tri_state"))
      (node (ref "IC15") (pin "2") (pinfunction "1Q_2") (pintype "tri_state"))
      (node (ref "IC16") (pin "2") (pinfunction "1Q_2") (pintype "tri_state"))
      (node (ref "IC17") (pin "2") (pinfunction "1Q_2") (pintype "tri_state"))
      (node (ref "IC18") (pin "2") (pinfunction "1Q_2") (pintype "tri_state"))
      (node (ref "IC2") (pin "3") (pinfunction "1D_3") (pintype "input"))
      (node (ref "IC3") (pin "3") (pinfunction "1D_3") (pintype "input"))
      (node (ref "IC4") (pin "3") (pinfunction "1D_3") (pintype "input"))
      (node (ref "IC5") (pin "3") (pinfunction "1D_3") (pintype "input"))
      (node (ref "IC6") (pin "3") (pinfunction "1D_3") (pintype "input"))
      (node (ref "IC7") (pin "3") (pinfunction "1D_3") (pintype "input"))
      (node (ref "IC8") (pin "3") (pinfunction "1D_3") (pintype "input"))
    )
    (net (code "156") (name "PIA-A1") (class "Default")
      (node (ref "CORE-IO") (pin "2") (pinfunction "2_2") (pintype "passive"))
      (node (ref "IC1") (pin "4") (pinfunction "2D_4") (pintype "input"))
      (node (ref "IC11") (pin "5") (pinfunction "2Q_5") (pintype "tri_state"))
      (node (ref "IC12") (pin "5") (pinfunction "2Q_5") (pintype "tri_state"))
      (node (ref "IC13") (pin "5") (pinfunction "2Q_5") (pintype "tri_state"))
      (node (ref "IC14") (pin "5") (pinfunction "2Q_5") (pintype "tri_state"))
      (node (ref "IC15") (pin "5") (pinfunction "2Q_5") (pintype "tri_state"))
      (node (ref "IC16") (pin "5") (pinfunction "2Q_5") (pintype "tri_state"))
      (node (ref "IC17") (pin "5") (pinfunction "2Q_5") (pintype "tri_state"))
      (node (ref "IC18") (pin "5") (pinfunction "2Q_5") (pintype "tri_state"))
      (node (ref "IC2") (pin "4") (pinfunction "2D_4") (pintype "input"))
      (node (ref "IC3") (pin "4") (pinfunction "2D_4") (pintype "input"))
      (node (ref "IC4") (pin "4") (pinfunction "2D_4") (pintype "input"))
      (node (ref "IC5") (pin "4") (pinfunction "2D_4") (pintype "input"))
      (node (ref "IC6") (pin "4") (pinfunction "2D_4") (pintype "input"))
      (node (ref "IC7") (pin "4") (pinfunction "2D_4") (pintype "input"))
      (node (ref "IC8") (pin "4") (pinfunction "2D_4") (pintype "input"))
    )
    (net (code "157") (name "PIA-A2") (class "Default")
      (node (ref "CORE-IO") (pin "3") (pinfunction "3_3") (pintype "passive"))
      (node (ref "IC1") (pin "7") (pinfunction "3D_7") (pintype "input"))
      (node (ref "IC11") (pin "6") (pinfunction "3Q_6") (pintype "tri_state"))
      (node (ref "IC12") (pin "6") (pinfunction "3Q_6") (pintype "tri_state"))
      (node (ref "IC13") (pin "6") (pinfunction "3Q_6") (pintype "tri_state"))
      (node (ref "IC14") (pin "6") (pinfunction "3Q_6") (pintype "tri_state"))
      (node (ref "IC15") (pin "6") (pinfunction "3Q_6") (pintype "tri_state"))
      (node (ref "IC16") (pin "6") (pinfunction "3Q_6") (pintype "tri_state"))
      (node (ref "IC17") (pin "6") (pinfunction "3Q_6") (pintype "tri_state"))
      (node (ref "IC18") (pin "6") (pinfunction "3Q_6") (pintype "tri_state"))
      (node (ref "IC2") (pin "7") (pinfunction "3D_7") (pintype "input"))
      (node (ref "IC3") (pin "7") (pinfunction "3D_7") (pintype "input"))
      (node (ref "IC4") (pin "7") (pinfunction "3D_7") (pintype "input"))
      (node (ref "IC5") (pin "7") (pinfunction "3D_7") (pintype "input"))
      (node (ref "IC6") (pin "7") (pinfunction "3D_7") (pintype "input"))
      (node (ref "IC7") (pin "7") (pinfunction "3D_7") (pintype "input"))
      (node (ref "IC8") (pin "7") (pinfunction "3D_7") (pintype "input"))
    )
    (net (code "158") (name "PIA-A3") (class "Default")
      (node (ref "CORE-IO") (pin "4") (pinfunction "4_4") (pintype "passive"))
      (node (ref "IC1") (pin "8") (pinfunction "4D_8") (pintype "input"))
      (node (ref "IC11") (pin "9") (pinfunction "4Q_9") (pintype "tri_state"))
      (node (ref "IC12") (pin "9") (pinfunction "4Q_9") (pintype "tri_state"))
      (node (ref "IC13") (pin "9") (pinfunction "4Q_9") (pintype "tri_state"))
      (node (ref "IC14") (pin "9") (pinfunction "4Q_9") (pintype "tri_state"))
      (node (ref "IC15") (pin "9") (pinfunction "4Q_9") (pintype "tri_state"))
      (node (ref "IC16") (pin "9") (pinfunction "4Q_9") (pintype "tri_state"))
      (node (ref "IC17") (pin "9") (pinfunction "4Q_9") (pintype "tri_state"))
      (node (ref "IC18") (pin "9") (pinfunction "4Q_9") (pintype "tri_state"))
      (node (ref "IC2") (pin "8") (pinfunction "4D_8") (pintype "input"))
      (node (ref "IC3") (pin "8") (pinfunction "4D_8") (pintype "input"))
      (node (ref "IC4") (pin "8") (pinfunction "4D_8") (pintype "input"))
      (node (ref "IC5") (pin "8") (pinfunction "4D_8") (pintype "input"))
      (node (ref "IC6") (pin "8") (pinfunction "4D_8") (pintype "input"))
      (node (ref "IC7") (pin "8") (pinfunction "4D_8") (pintype "input"))
      (node (ref "IC8") (pin "8") (pinfunction "4D_8") (pintype "input"))
    )
    (net (code "159") (name "PIA-A4") (class "Default")
      (node (ref "CORE-IO") (pin "5") (pinfunction "5_5") (pintype "passive"))
      (node (ref "IC1") (pin "13") (pinfunction "5D_13") (pintype "input"))
      (node (ref "IC11") (pin "12") (pinfunction "5Q_12") (pintype "tri_state"))
      (node (ref "IC12") (pin "12") (pinfunction "5Q_12") (pintype "tri_state"))
      (node (ref "IC13") (pin "12") (pinfunction "5Q_12") (pintype "tri_state"))
      (node (ref "IC14") (pin "12") (pinfunction "5Q_12") (pintype "tri_state"))
      (node (ref "IC15") (pin "12") (pinfunction "5Q_12") (pintype "tri_state"))
      (node (ref "IC16") (pin "12") (pinfunction "5Q_12") (pintype "tri_state"))
      (node (ref "IC17") (pin "12") (pinfunction "5Q_12") (pintype "tri_state"))
      (node (ref "IC18") (pin "12") (pinfunction "5Q_12") (pintype "tri_state"))
      (node (ref "IC2") (pin "13") (pinfunction "5D_13") (pintype "input"))
      (node (ref "IC3") (pin "13") (pinfunction "5D_13") (pintype "input"))
      (node (ref "IC4") (pin "13") (pinfunction "5D_13") (pintype "input"))
      (node (ref "IC5") (pin "13") (pinfunction "5D_13") (pintype "input"))
      (node (ref "IC6") (pin "13") (pinfunction "5D_13") (pintype "input"))
      (node (ref "IC7") (pin "13") (pinfunction "5D_13") (pintype "input"))
      (node (ref "IC8") (pin "13") (pinfunction "5D_13") (pintype "input"))
    )
    (net (code "160") (name "PIA-A5") (class "Default")
      (node (ref "CORE-IO") (pin "6") (pinfunction "6_6") (pintype "passive"))
      (node (ref "IC1") (pin "14") (pinfunction "6D_14") (pintype "input"))
      (node (ref "IC11") (pin "15") (pinfunction "6Q_15") (pintype "tri_state"))
      (node (ref "IC12") (pin "15") (pinfunction "6Q_15") (pintype "tri_state"))
      (node (ref "IC13") (pin "15") (pinfunction "6Q_15") (pintype "tri_state"))
      (node (ref "IC14") (pin "15") (pinfunction "6Q_15") (pintype "tri_state"))
      (node (ref "IC15") (pin "15") (pinfunction "6Q_15") (pintype "tri_state"))
      (node (ref "IC16") (pin "15") (pinfunction "6Q_15") (pintype "tri_state"))
      (node (ref "IC17") (pin "15") (pinfunction "6Q_15") (pintype "tri_state"))
      (node (ref "IC18") (pin "15") (pinfunction "6Q_15") (pintype "tri_state"))
      (node (ref "IC2") (pin "14") (pinfunction "6D_14") (pintype "input"))
      (node (ref "IC3") (pin "14") (pinfunction "6D_14") (pintype "input"))
      (node (ref "IC4") (pin "14") (pinfunction "6D_14") (pintype "input"))
      (node (ref "IC5") (pin "14") (pinfunction "6D_14") (pintype "input"))
      (node (ref "IC6") (pin "14") (pinfunction "6D_14") (pintype "input"))
      (node (ref "IC7") (pin "14") (pinfunction "6D_14") (pintype "input"))
      (node (ref "IC8") (pin "14") (pinfunction "6D_14") (pintype "input"))
    )
    (net (code "161") (name "PIA-A6") (class "Default")
      (node (ref "CORE-IO") (pin "7") (pinfunction "7_7") (pintype "passive"))
      (node (ref "IC1") (pin "17") (pinfunction "7D_17") (pintype "input"))
      (node (ref "IC11") (pin "16") (pinfunction "7Q_16") (pintype "tri_state"))
      (node (ref "IC12") (pin "16") (pinfunction "7Q_16") (pintype "tri_state"))
      (node (ref "IC13") (pin "16") (pinfunction "7Q_16") (pintype "tri_state"))
      (node (ref "IC14") (pin "16") (pinfunction "7Q_16") (pintype "tri_state"))
      (node (ref "IC15") (pin "16") (pinfunction "7Q_16") (pintype "tri_state"))
      (node (ref "IC16") (pin "16") (pinfunction "7Q_16") (pintype "tri_state"))
      (node (ref "IC17") (pin "16") (pinfunction "7Q_16") (pintype "tri_state"))
      (node (ref "IC18") (pin "16") (pinfunction "7Q_16") (pintype "tri_state"))
      (node (ref "IC2") (pin "17") (pinfunction "7D_17") (pintype "input"))
      (node (ref "IC3") (pin "17") (pinfunction "7D_17") (pintype "input"))
      (node (ref "IC4") (pin "17") (pinfunction "7D_17") (pintype "input"))
      (node (ref "IC5") (pin "17") (pinfunction "7D_17") (pintype "input"))
      (node (ref "IC6") (pin "17") (pinfunction "7D_17") (pintype "input"))
      (node (ref "IC7") (pin "17") (pinfunction "7D_17") (pintype "input"))
      (node (ref "IC8") (pin "17") (pinfunction "7D_17") (pintype "input"))
    )
    (net (code "162") (name "PIA-A7") (class "Default")
      (node (ref "CORE-IO") (pin "8") (pinfunction "8_8") (pintype "passive"))
      (node (ref "IC1") (pin "18") (pinfunction "8D_18") (pintype "input"))
      (node (ref "IC11") (pin "19") (pinfunction "8Q_19") (pintype "tri_state"))
      (node (ref "IC12") (pin "19") (pinfunction "8Q_19") (pintype "tri_state"))
      (node (ref "IC13") (pin "19") (pinfunction "8Q_19") (pintype "tri_state"))
      (node (ref "IC14") (pin "19") (pinfunction "8Q_19") (pintype "tri_state"))
      (node (ref "IC15") (pin "19") (pinfunction "8Q_19") (pintype "tri_state"))
      (node (ref "IC16") (pin "19") (pinfunction "8Q_19") (pintype "tri_state"))
      (node (ref "IC17") (pin "19") (pinfunction "8Q_19") (pintype "tri_state"))
      (node (ref "IC18") (pin "19") (pinfunction "8Q_19") (pintype "tri_state"))
      (node (ref "IC2") (pin "18") (pinfunction "8D_18") (pintype "input"))
      (node (ref "IC3") (pin "18") (pinfunction "8D_18") (pintype "input"))
      (node (ref "IC4") (pin "18") (pinfunction "8D_18") (pintype "input"))
      (node (ref "IC5") (pin "18") (pinfunction "8D_18") (pintype "input"))
      (node (ref "IC6") (pin "18") (pinfunction "8D_18") (pintype "input"))
      (node (ref "IC7") (pin "18") (pinfunction "8D_18") (pintype "input"))
      (node (ref "IC8") (pin "18") (pinfunction "8D_18") (pintype "input"))
    )
    (net (code "163") (name "PIA-B0") (class "Default")
      (node (ref "CORE-IO") (pin "13") (pinfunction "13_13") (pintype "passive"))
      (node (ref "IC10") (pin "1") (pinfunction "A_1") (pintype "input"))
      (node (ref "IC9") (pin "1") (pinfunction "A_1") (pintype "input"))
    )
    (net (code "164") (name "PIA-B1") (class "Default")
      (node (ref "CORE-IO") (pin "14") (pinfunction "14_14") (pintype "passive"))
      (node (ref "IC10") (pin "2") (pinfunction "B_2") (pintype "input"))
      (node (ref "IC9") (pin "2") (pinfunction "B_2") (pintype "input"))
    )
    (net (code "165") (name "PIA-B2") (class "Default")
      (node (ref "CORE-IO") (pin "15") (pinfunction "15_15") (pintype "passive"))
      (node (ref "IC10") (pin "3") (pinfunction "C_3") (pintype "input"))
      (node (ref "IC9") (pin "3") (pinfunction "C_3") (pintype "input"))
    )
    (net (code "166") (name "PIA-B3") (class "Default")
      (node (ref "CORE-IO") (pin "16") (pinfunction "16_16") (pintype "passive"))
      (node (ref "IC19") (pin "1") (pinfunction "A_1") (pintype "input"))
    )
    (net (code "167") (name "PIA-B4") (class "Default")
      (node (ref "CORE-IO") (pin "17") (pinfunction "17_17") (pintype "passive"))
      (node (ref "IC19") (pin "2") (pinfunction "B_2") (pintype "input"))
    )
    (net (code "168") (name "PIA-B5") (class "Default")
      (node (ref "CORE-IO") (pin "18") (pinfunction "18_18") (pintype "passive"))
      (node (ref "IC19") (pin "3") (pinfunction "C_3") (pintype "input"))
    )
    (net (code "169") (name "PIA-B6") (class "Default")
      (node (ref "CORE-IO") (pin "19") (pinfunction "19_19") (pintype "passive"))
      (node (ref "IC10") (pin "6") (pinfunction "G1_6") (pintype "input"))
      (node (ref "IC9") (pin "4") (pinfunction "G2A_4") (pintype "input"))
    )
    (net (code "170") (name "PIA-B7") (class "Default")
      (node (ref "CORE-IO") (pin "20") (pinfunction "20_20") (pintype "passive"))
      (node (ref "DEVSEL") (pin "2") (pinfunction "2_2") (pintype "passive"))
      (node (ref "IC19") (pin "5") (pinfunction "G2B_5") (pintype "input"))
    )
    (net (code "171") (name "VCC") (class "Default")
      (node (ref "BYP1") (pin "1") (pinfunction "1_1") (pintype "passive"))
      (node (ref "BYP10") (pin "1") (pinfunction "1_1") (pintype "passive"))
      (node (ref "BYP11") (pin "1") (pinfunction "1_1") (pintype "passive"))
      (node (ref "BYP12") (pin "1") (pinfunction "1_1") (pintype "passive"))
      (node (ref "BYP13") (pin "1") (pinfunction "1_1") (pintype "passive"))
      (node (ref "BYP14") (pin "1") (pinfunction "1_1") (pintype "passive"))
      (node (ref "BYP15") (pin "1") (pinfunction "1_1") (pintype "passive"))
      (node (ref "BYP16") (pin "1") (pinfunction "1_1") (pintype "passive"))
      (node (ref "BYP17") (pin "1") (pinfunction "1_1") (pintype "passive"))
      (node (ref "BYP18") (pin "1") (pinfunction "1_1") (pintype "passive"))
      (node (ref "BYP19") (pin "1") (pinfunction "1_1") (pintype "passive"))
      (node (ref "BYP2") (pin "1") (pinfunction "1_1") (pintype "passive"))
      (node (ref "BYP20") (pin "1") (pinfunction "1_1") (pintype "passive"))
      (node (ref "BYP3") (pin "1") (pinfunction "1_1") (pintype "passive"))
      (node (ref "BYP4") (pin "1") (pinfunction "1_1") (pintype "passive"))
      (node (ref "BYP5") (pin "1") (pinfunction "1_1") (pintype "passive"))
      (node (ref "BYP6") (pin "1") (pinfunction "1_1") (pintype "passive"))
      (node (ref "BYP7") (pin "1") (pinfunction "1_1") (pintype "passive"))
      (node (ref "BYP8") (pin "1") (pinfunction "1_1") (pintype "passive"))
      (node (ref "BYP9") (pin "1") (pinfunction "1_1") (pintype "passive"))
      (node (ref "CORE-IO") (pin "12") (pinfunction "12_12") (pintype "passive"))
      (node (ref "CORE-IO") (pin "9") (pinfunction "9_9") (pintype "passive"))
      (node (ref "IC11") (pin "11") (pinfunction "ENC_11") (pintype "input"))
      (node (ref "IC12") (pin "11") (pinfunction "ENC_11") (pintype "input"))
      (node (ref "IC13") (pin "11") (pinfunction "ENC_11") (pintype "input"))
      (node (ref "IC14") (pin "11") (pinfunction "ENC_11") (pintype "input"))
      (node (ref "IC15") (pin "11") (pinfunction "ENC_11") (pintype "input"))
      (node (ref "IC16") (pin "11") (pinfunction "ENC_11") (pintype "input"))
      (node (ref "IC17") (pin "11") (pinfunction "ENC_11") (pintype "input"))
      (node (ref "IC18") (pin "11") (pinfunction "ENC_11") (pintype "input"))
      (node (ref "IC19") (pin "6") (pinfunction "G1_6") (pintype "input"))
      (node (ref "IC9") (pin "6") (pinfunction "G1_6") (pintype "input"))
      (node (ref "JP2") (pin "2") (pinfunction "2_2") (pintype "passive"))
    )
  )
)
